# DigitalMaze.net
KiCad netlist of a schematic drawn in Altium Designer
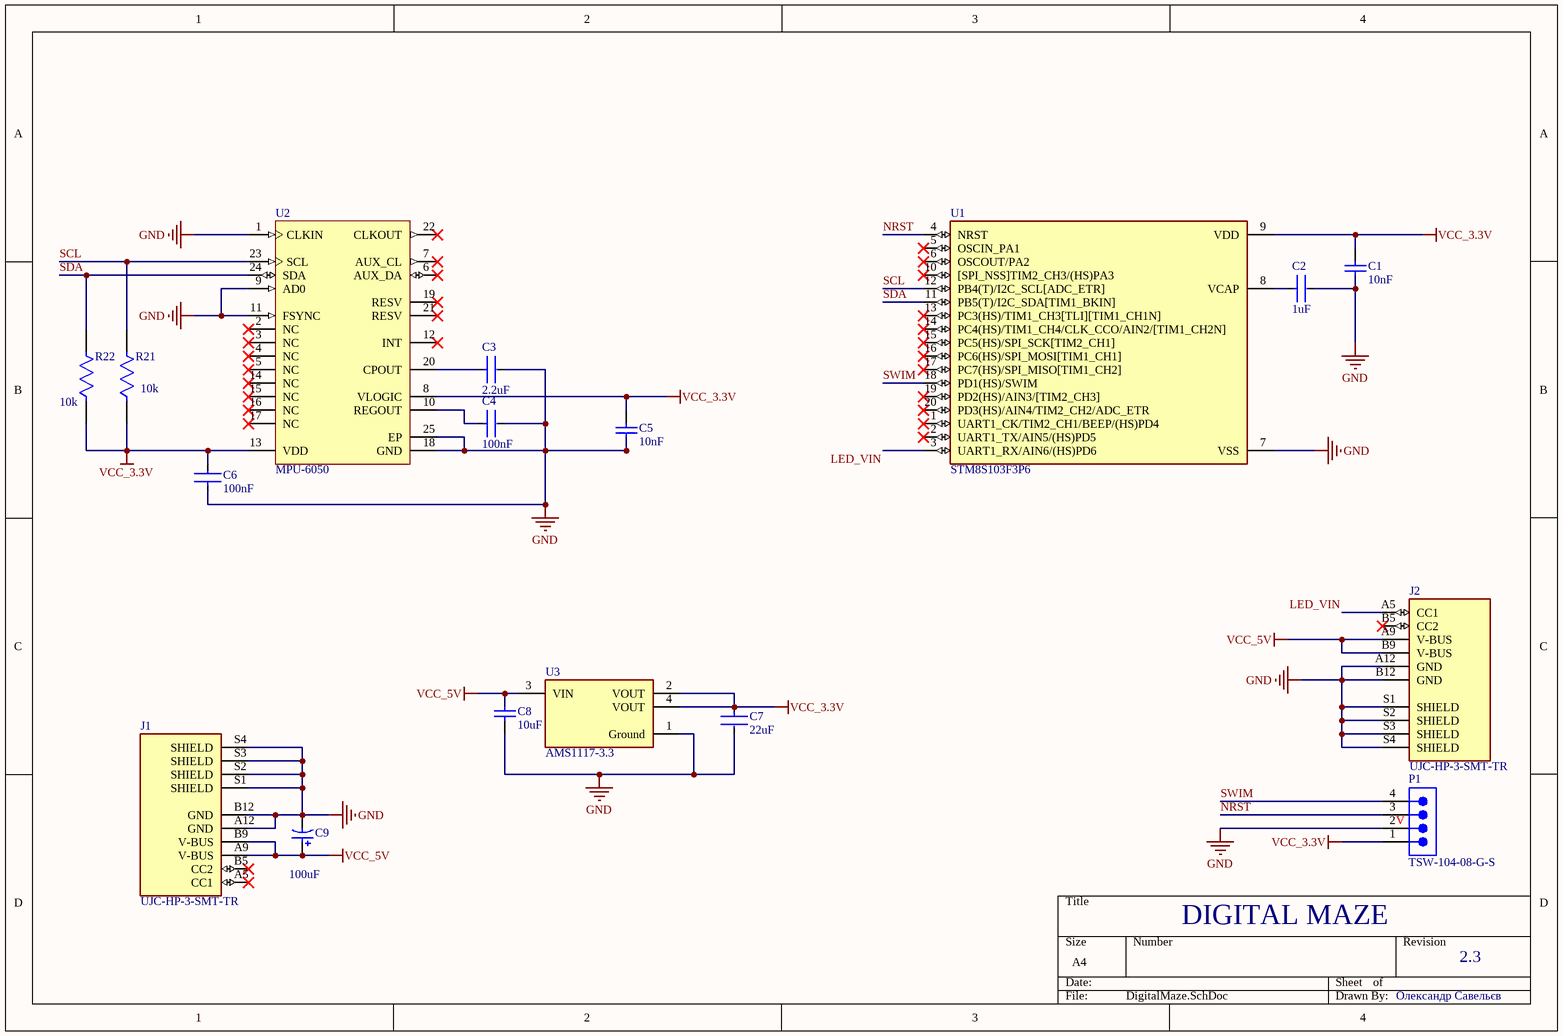
[diagram p0: DigitalMaze.SchDoc]

(export (version "E")
  (design (tool "Eeschema 10.0.6"))
  (components
    (comp (ref "C1")
      (value "10nF")
      (footprint "CAPC1206(3216)150_N")
      (description "CAP 10nF 25V ±10% 1206 (3216 Metric) Thickness 1.45mm SMD")
      (fields (field (name "TOLERANCE") "Â±10%"))
      (libsource (lib "Altium Content Vault") (part "CAP"))
    )
    (comp (ref "C2")
      (value "1uF")
      (footprint "FP-CGA5L-0_3-0_1-MFG")
      (description "Cap Ceramic 1uF 25V X7R 10% Pad SMD 1206 +125°C Automotive T/R")
      (fields (field (name "TOLERANCE") "10%"))
      (libsource (lib "Altium Content Vault") (part "b4654b650e69147ec39a6b967a45e02"))
    )
    (comp (ref "C3")
      (value "2.2uF")
      (footprint "FP-1206-L_3_2_0_15-W_1_6-MFG")
      (description "None")
      (fields (field (name "VOLTAGE") "50V") (field (name "TOLERANCE") "20%"))
      (libsource (lib "Altium Content Vault") (part "02cd4be3c70576c341d710602a673aa"))
    )
    (comp (ref "C4")
      (value "100nF")
      (footprint "FP-C1206C-EB-MFG")
      (description "C1206 0.10 μF U2J 20.00% 50 V")
      (fields
        (field (name "OCTOPART") "https://octopart.com/c1206c104m5jacauto-kemet-84732526")
        (field (name "MANUFACTURER") "KEMET")
      )
      (libsource (lib "Altium Content Vault") (part "b4654b650e69147ec39a6b967a45e02"))
    )
    (comp (ref "C5")
      (value "10nF")
      (footprint "CAPC1206(3216)150_N")
      (description "CAP 10nF 25V ±10% 1206 (3216 Metric) Thickness 1.45mm SMD")
      (fields (field (name "TOLERANCE") "Â±10%"))
      (libsource (lib "Altium Content Vault") (part "CAP"))
    )
    (comp (ref "C6")
      (value "100nF")
      (footprint "FP-C1206C-EB-MFG")
      (description "C1206 0.10 μF U2J 20.00% 50 V")
      (fields
        (field (name "OCTOPART") "https://octopart.com/c1206c104m5jacauto-kemet-84732526")
        (field (name "MANUFACTURER") "KEMET")
      )
      (libsource (lib "Altium Content Vault") (part "b4654b650e69147ec39a6b967a45e02"))
    )
    (comp (ref "C7")
      (value "22uF")
      (footprint "FP-GRM21B-0_2-e0_2_0_7-MFG")
      (description "Chip Multilayer Ceramic Capacitors for General Purpose, 0805, 22uF, X5R, 15%, 20%, 25V")
      (fields (field (name "TOLERANCE") "20%"))
      (libsource (lib "Altium Content Vault") (part "b4654b650e69147ec39a6b967a45e02"))
    )
    (comp (ref "C8")
      (value "10uF")
      (footprint "CAPC1206(3216)190_N")
      (description "CAP 10uF 25V ±20% 1206 (3216 Metric) Thickness 1.9mm SMD")
      (fields (field (name "TOLERANCE") "Â±20%"))
      (libsource (lib "Altium Content Vault") (part "CAP"))
    )
    (comp (ref "C9")
      (value "100uF")
      (footprint "PNSC-FK-V-D8_V")
      (fields (field (name "MANUFACTURER") "Panasonic"))
      (libsource (lib "Altium Content Vault") (part "CAP-P-2"))
    )
    (comp (ref "J1")
      (value "UJC-HP-3-SMT-TR")
      (footprint "CUI_UJC-HP-3-SMT-TR")
      (libsource (lib "") (part "UJC-HP-3-SMT-TR_1"))
    )
    (comp (ref "J2")
      (value "UJC-HP-3-SMT-TR")
      (footprint "CUI_UJC-HP-3-SMT-TR")
      (libsource (lib "UJC-HP-3-SMT-TR") (part "UJC-HP-3-SMT-TR"))
    )
    (comp (ref "P1")
      (value "TSW-104-08-G-S")
      (footprint "SMTC-TSW-104-08-X-S")
      (description "0.025\" SQ Post Header, Through-hole, Vertical, -55 to 125 degC, 2.54 mm Pitch, 4-Pin, Male, RoHS")
      (fields (field (name "MANUFACTURER") "Samtec"))
      (libsource (lib "Altium Content Vault") (part "SMTC-TSW-104-08-X-S"))
    )
    (comp (ref "R21")
      (value "10k")
      (footprint "FP-RT1206-MFG")
      (description "RES SMD 10K OHM 0.1% 1/4W 1206")
      (fields
        (field (name "MANUFACTURER") "Yageo")
        (field (name "OCTOPART") "https://octopart.com/rt1206brc0710kl-yageo-30512400")
      )
      (libsource (lib "Altium Content Vault") (part "1029c3af85768c4190bb7ad29bc67b5"))
    )
    (comp (ref "R22")
      (value "10k")
      (footprint "FP-RT1206-MFG")
      (description "RES SMD 10K OHM 0.1% 1/4W 1206")
      (fields
        (field (name "MANUFACTURER") "Yageo")
        (field (name "OCTOPART") "https://octopart.com/rt1206brc0710kl-yageo-30512400")
      )
      (libsource (lib "Altium Content Vault") (part "1029c3af85768c4190bb7ad29bc67b5"))
    )
    (comp (ref "U1")
      (value "STM8S103F3P6")
      (footprint "SOP65P640X120-20N")
      (description "STM8 series Microcontroller IC 8-Bit 16MHz 8KB (8K x 8) FLASH 20-TSSOP")
      (fields (field (name "MF") "STMicroelectronics"))
      (libsource (lib "STM8S103F3P6") (part "STM8S103F3P6"))
    )
    (comp (ref "U2")
      (value "MPU-6050")
      (footprint "IS-QFN-24_V")
      (fields (field (name "MANUFACTURER") "InvenSense"))
      (libsource (lib "Altium Content Vault") (part "IS-MPU-6050-QFN-24"))
    )
    (comp (ref "U3")
      (value "AMS1117-3.3")
      (footprint "FP-AMS1117-IPC_C")
      (description "LDO Voltage Regulators 1A, 3.3V")
      (fields
        (field (name "OCTOPART") "https://octopart.com/ams1117-3.3-advanced+monolithic+systems-25899300")
        (field (name "MANUFACTURER") "Advanced Monolithic Systems")
      )
      (libsource (lib "Altium Content Vault") (part "8bdbb5f8e77002000e30dd2845d0354"))
    )
  )
  (nets
    (net (code "1") (name "/LED_VIN") (class "Default")
      (node (ref "J2") (pin "A5") (pinfunction "CC1_A5") (pintype "bidirectional"))
      (node (ref "U1") (pin "3") (pinfunction "UART1_RX/AIN6/(HS)PD6_3") (pintype "bidirectional"))
    )
    (net (code "2") (name "/NRST") (class "Default")
      (node (ref "P1") (pin "3") (pinfunction "3_3") (pintype "passive"))
      (node (ref "U1") (pin "4") (pinfunction "NRST_4") (pintype "bidirectional"))
    )
    (net (code "3") (name "/SCL") (class "Default")
      (node (ref "R21") (pin "2") (pinfunction "2_2") (pintype "passive"))
      (node (ref "U1") (pin "12") (pinfunction "PB4(T)/I2C_SCL[ADC_ETR]_12") (pintype "bidirectional"))
      (node (ref "U2") (pin "23") (pinfunction "SCL_23") (pintype "input"))
    )
    (net (code "4") (name "/SDA") (class "Default")
      (node (ref "R22") (pin "2") (pinfunction "2_2") (pintype "passive"))
      (node (ref "U1") (pin "11") (pinfunction "PB5(T)/I2C_SDA[TIM1_BKIN]_11") (pintype "bidirectional"))
      (node (ref "U2") (pin "24") (pinfunction "SDA_24") (pintype "bidirectional"))
    )
    (net (code "5") (name "/SWIM") (class "Default")
      (node (ref "P1") (pin "4") (pinfunction "4_4") (pintype "passive"))
      (node (ref "U1") (pin "18") (pinfunction "PD1(HS)/SWIM_18") (pintype "bidirectional"))
    )
    (net (code "6") (name "GND") (class "Default")
      (node (ref "C1") (pin "1") (pinfunction "1_1") (pintype "passive"))
      (node (ref "C2") (pin "2") (pinfunction "2_2") (pintype "passive"))
      (node (ref "C3") (pin "2") (pinfunction "2_2") (pintype "passive"))
      (node (ref "C4") (pin "2") (pinfunction "2_2") (pintype "passive"))
      (node (ref "C5") (pin "1") (pinfunction "1_1") (pintype "passive"))
      (node (ref "C6") (pin "1") (pinfunction "1_1") (pintype "passive"))
      (node (ref "C7") (pin "2") (pinfunction "2_2") (pintype "passive"))
      (node (ref "C8") (pin "1") (pinfunction "1_1") (pintype "passive"))
      (node (ref "C9") (pin "2") (pinfunction "2_2") (pintype "passive"))
      (node (ref "J1") (pin "A12") (pinfunction "GND_A12") (pintype "power_in"))
      (node (ref "J1") (pin "B12") (pinfunction "GND_B12") (pintype "power_in"))
      (node (ref "J1") (pin "S1") (pinfunction "SHIELD_S1") (pintype "passive"))
      (node (ref "J1") (pin "S2") (pinfunction "SHIELD_S2") (pintype "passive"))
      (node (ref "J1") (pin "S3") (pinfunction "SHIELD_S3") (pintype "passive"))
      (node (ref "J1") (pin "S4") (pinfunction "SHIELD_S4") (pintype "passive"))
      (node (ref "J2") (pin "A12") (pinfunction "GND_A12") (pintype "power_in"))
      (node (ref "J2") (pin "B12") (pinfunction "GND_B12") (pintype "power_in"))
      (node (ref "J2") (pin "S1") (pinfunction "SHIELD_S1") (pintype "passive"))
      (node (ref "J2") (pin "S2") (pinfunction "SHIELD_S2") (pintype "passive"))
      (node (ref "J2") (pin "S3") (pinfunction "SHIELD_S3") (pintype "passive"))
      (node (ref "J2") (pin "S4") (pinfunction "SHIELD_S4") (pintype "passive"))
      (node (ref "P1") (pin "2") (pinfunction "2_2") (pintype "passive"))
      (node (ref "U1") (pin "7") (pinfunction "VSS_7") (pintype "power_in"))
      (node (ref "U2") (pin "1") (pinfunction "CLKIN_1") (pintype "input"))
      (node (ref "U2") (pin "11") (pinfunction "FSYNC_11") (pintype "input"))
      (node (ref "U2") (pin "18") (pinfunction "GND_18") (pintype "power_in"))
      (node (ref "U2") (pin "25") (pinfunction "EP_25") (pintype "power_in"))
      (node (ref "U2") (pin "9") (pinfunction "AD0_9") (pintype "input"))
      (node (ref "U3") (pin "1") (pinfunction "Ground_1") (pintype "power_in"))
    )
    (net (code "7") (name "Net-(U1-VCAP)") (class "Default")
      (node (ref "C2") (pin "1") (pinfunction "1_1") (pintype "passive"))
      (node (ref "U1") (pin "8") (pinfunction "VCAP_8") (pintype "passive"))
    )
    (net (code "8") (name "Net-(U2-CPOUT)") (class "Default")
      (node (ref "C3") (pin "1") (pinfunction "1_1") (pintype "passive"))
      (node (ref "U2") (pin "20") (pinfunction "CPOUT_20") (pintype "passive"))
    )
    (net (code "9") (name "Net-(U2-REGOUT)") (class "Default")
      (node (ref "C4") (pin "1") (pinfunction "1_1") (pintype "passive"))
      (node (ref "U2") (pin "10") (pinfunction "REGOUT_10") (pintype "passive"))
    )
    (net (code "10") (name "VCC_3.3V") (class "Default")
      (node (ref "C1") (pin "2") (pinfunction "2_2") (pintype "passive"))
      (node (ref "C5") (pin "2") (pinfunction "2_2") (pintype "passive"))
      (node (ref "C6") (pin "2") (pinfunction "2_2") (pintype "passive"))
      (node (ref "C7") (pin "1") (pinfunction "1_1") (pintype "passive"))
      (node (ref "P1") (pin "1") (pinfunction "1_1") (pintype "passive"))
      (node (ref "R21") (pin "1") (pinfunction "1_1") (pintype "passive"))
      (node (ref "R22") (pin "1") (pinfunction "1_1") (pintype "passive"))
      (node (ref "U1") (pin "9") (pinfunction "VDD_9") (pintype "power_in"))
      (node (ref "U2") (pin "13") (pinfunction "VDD_13") (pintype "power_in"))
      (node (ref "U2") (pin "8") (pinfunction "VLOGIC_8") (pintype "power_in"))
      (node (ref "U3") (pin "2") (pinfunction "VOUT_2") (pintype "passive"))
      (node (ref "U3") (pin "4") (pinfunction "VOUT_4") (pintype "passive"))
    )
    (net (code "11") (name "VCC_5V") (class "Default")
      (node (ref "C8") (pin "2") (pinfunction "2_2") (pintype "passive"))
      (node (ref "C9") (pin "1") (pinfunction "1_1") (pintype "passive"))
      (node (ref "J1") (pin "A9") (pinfunction "V-BUS_A9") (pintype "power_in"))
      (node (ref "J1") (pin "B9") (pinfunction "V-BUS_B9") (pintype "power_in"))
      (node (ref "J2") (pin "A9") (pinfunction "V-BUS_A9") (pintype "power_in"))
      (node (ref "J2") (pin "B9") (pinfunction "V-BUS_B9") (pintype "power_in"))
      (node (ref "U3") (pin "3") (pinfunction "VIN_3") (pintype "power_in"))
    )
    (net (code "12") (name "unconnected-(J1-CC1-PadA5)") (class "Default")
      (node (ref "J1") (pin "A5") (pinfunction "CC1_A5") (pintype "bidirectional+no_connect"))
    )
    (net (code "13") (name "unconnected-(J1-CC2-PadB5)") (class "Default")
      (node (ref "J1") (pin "B5") (pinfunction "CC2_B5") (pintype "bidirectional+no_connect"))
    )
    (net (code "14") (name "unconnected-(J2-CC2-PadB5)") (class "Default")
      (node (ref "J2") (pin "B5") (pinfunction "CC2_B5") (pintype "bidirectional+no_connect"))
    )
    (net (code "15") (name "unconnected-(U1-OSCIN_PA1-Pad5)") (class "Default")
      (node (ref "U1") (pin "5") (pinfunction "OSCIN_PA1_5") (pintype "bidirectional+no_connect"))
    )
    (net (code "16") (name "unconnected-(U1-OSCOUT{slash}PA2-Pad6)") (class "Default")
      (node (ref "U1") (pin "6") (pinfunction "OSCOUT/PA2_6") (pintype "bidirectional+no_connect"))
    )
    (net (code "17") (name "unconnected-(U1-PC3(HS){slash}TIM1_CH3[TLI][TIM1_CH1N]-Pad13)") (class "Default")
      (node (ref "U1") (pin "13") (pinfunction "PC3(HS)/TIM1_CH3[TLI][TIM1_CH1N]_13") (pintype "bidirectional+no_connect"))
    )
    (net (code "18") (name "unconnected-(U1-PC4(HS){slash}TIM1_CH4{slash}CLK_CCO{slash}AIN2{slash}[TIM1_CH2N]-Pad14)") (class "Default")
      (node (ref "U1") (pin "14") (pinfunction "PC4(HS)/TIM1_CH4/CLK_CCO/AIN2/[TIM1_CH2N]_14") (pintype "bidirectional+no_connect"))
    )
    (net (code "19") (name "unconnected-(U1-PC5(HS){slash}SPI_SCK[TIM2_CH1]-Pad15)") (class "Default")
      (node (ref "U1") (pin "15") (pinfunction "PC5(HS)/SPI_SCK[TIM2_CH1]_15") (pintype "bidirectional+no_connect"))
    )
    (net (code "20") (name "unconnected-(U1-PC6(HS){slash}SPI_MOSI[TIM1_CH1]-Pad16)") (class "Default")
      (node (ref "U1") (pin "16") (pinfunction "PC6(HS)/SPI_MOSI[TIM1_CH1]_16") (pintype "bidirectional+no_connect"))
    )
    (net (code "21") (name "unconnected-(U1-PC7(HS){slash}SPI_MISO[TIM1_CH2]-Pad17)") (class "Default")
      (node (ref "U1") (pin "17") (pinfunction "PC7(HS)/SPI_MISO[TIM1_CH2]_17") (pintype "bidirectional+no_connect"))
    )
    (net (code "22") (name "unconnected-(U1-PD2(HS){slash}AIN3{slash}[TIM2_CH3]-Pad19)") (class "Default")
      (node (ref "U1") (pin "19") (pinfunction "PD2(HS)/AIN3/[TIM2_CH3]_19") (pintype "bidirectional+no_connect"))
    )
    (net (code "23") (name "unconnected-(U1-PD3(HS){slash}AIN4{slash}TIM2_CH2{slash}ADC_ETR-Pad20)") (class "Default")
      (node (ref "U1") (pin "20") (pinfunction "PD3(HS)/AIN4/TIM2_CH2/ADC_ETR_20") (pintype "bidirectional+no_connect"))
    )
    (net (code "24") (name "unconnected-(U1-UART1_CK{slash}TIM2_CH1{slash}BEEP{slash}(HS)PD4-Pad1)") (class "Default")
      (node (ref "U1") (pin "1") (pinfunction "UART1_CK/TIM2_CH1/BEEP/(HS)PD4_1") (pintype "bidirectional+no_connect"))
    )
    (net (code "25") (name "unconnected-(U1-UART1_TX{slash}AIN5{slash}(HS)PD5-Pad2)") (class "Default")
      (node (ref "U1") (pin "2") (pinfunction "UART1_TX/AIN5/(HS)PD5_2") (pintype "bidirectional+no_connect"))
    )
    (net (code "26") (name "unconnected-(U1-[SPI_NSS]TIM2_CH3{slash}(HS)PA3-Pad10)") (class "Default")
      (node (ref "U1") (pin "10") (pinfunction "[SPI_NSS]TIM2_CH3/(HS)PA3_10") (pintype "bidirectional+no_connect"))
    )
    (net (code "27") (name "unconnected-(U2-AUX_CL-Pad7)") (class "Default")
      (node (ref "U2") (pin "7") (pinfunction "AUX_CL_7") (pintype "output+no_connect"))
    )
    (net (code "28") (name "unconnected-(U2-AUX_DA-Pad6)") (class "Default")
      (node (ref "U2") (pin "6") (pinfunction "AUX_DA_6") (pintype "bidirectional+no_connect"))
    )
    (net (code "29") (name "unconnected-(U2-CLKOUT-Pad22)") (class "Default")
      (node (ref "U2") (pin "22") (pinfunction "CLKOUT_22") (pintype "output+no_connect"))
    )
    (net (code "30") (name "unconnected-(U2-INT-Pad12)") (class "Default")
      (node (ref "U2") (pin "12") (pinfunction "INT_12") (pintype "open_collector+no_connect"))
    )
    (net (code "31") (name "unconnected-(U2-NC-Pad2)") (class "Default")
      (node (ref "U2") (pin "2") (pinfunction "NC_2") (pintype "passive+no_connect"))
    )
    (net (code "32") (name "unconnected-(U2-NC-Pad3)") (class "Default")
      (node (ref "U2") (pin "3") (pinfunction "NC_3") (pintype "passive+no_connect"))
    )
    (net (code "33") (name "unconnected-(U2-NC-Pad4)") (class "Default")
      (node (ref "U2") (pin "4") (pinfunction "NC_4") (pintype "passive+no_connect"))
    )
    (net (code "34") (name "unconnected-(U2-NC-Pad5)") (class "Default")
      (node (ref "U2") (pin "5") (pinfunction "NC_5") (pintype "passive+no_connect"))
    )
    (net (code "35") (name "unconnected-(U2-NC-Pad14)") (class "Default")
      (node (ref "U2") (pin "14") (pinfunction "NC_14") (pintype "passive+no_connect"))
    )
    (net (code "36") (name "unconnected-(U2-NC-Pad15)") (class "Default")
      (node (ref "U2") (pin "15") (pinfunction "NC_15") (pintype "passive+no_connect"))
    )
    (net (code "37") (name "unconnected-(U2-NC-Pad16)") (class "Default")
      (node (ref "U2") (pin "16") (pinfunction "NC_16") (pintype "passive+no_connect"))
    )
    (net (code "38") (name "unconnected-(U2-NC-Pad17)") (class "Default")
      (node (ref "U2") (pin "17") (pinfunction "NC_17") (pintype "passive+no_connect"))
    )
    (net (code "39") (name "unconnected-(U2-RESV-Pad19)") (class "Default")
      (node (ref "U2") (pin "19") (pinfunction "RESV_19") (pintype "passive+no_connect"))
    )
    (net (code "40") (name "unconnected-(U2-RESV-Pad21)") (class "Default")
      (node (ref "U2") (pin "21") (pinfunction "RESV_21") (pintype "passive+no_connect"))
    )
  )
)
